# EspRelay.net
KiCad netlist of a schematic drawn in EAGLE
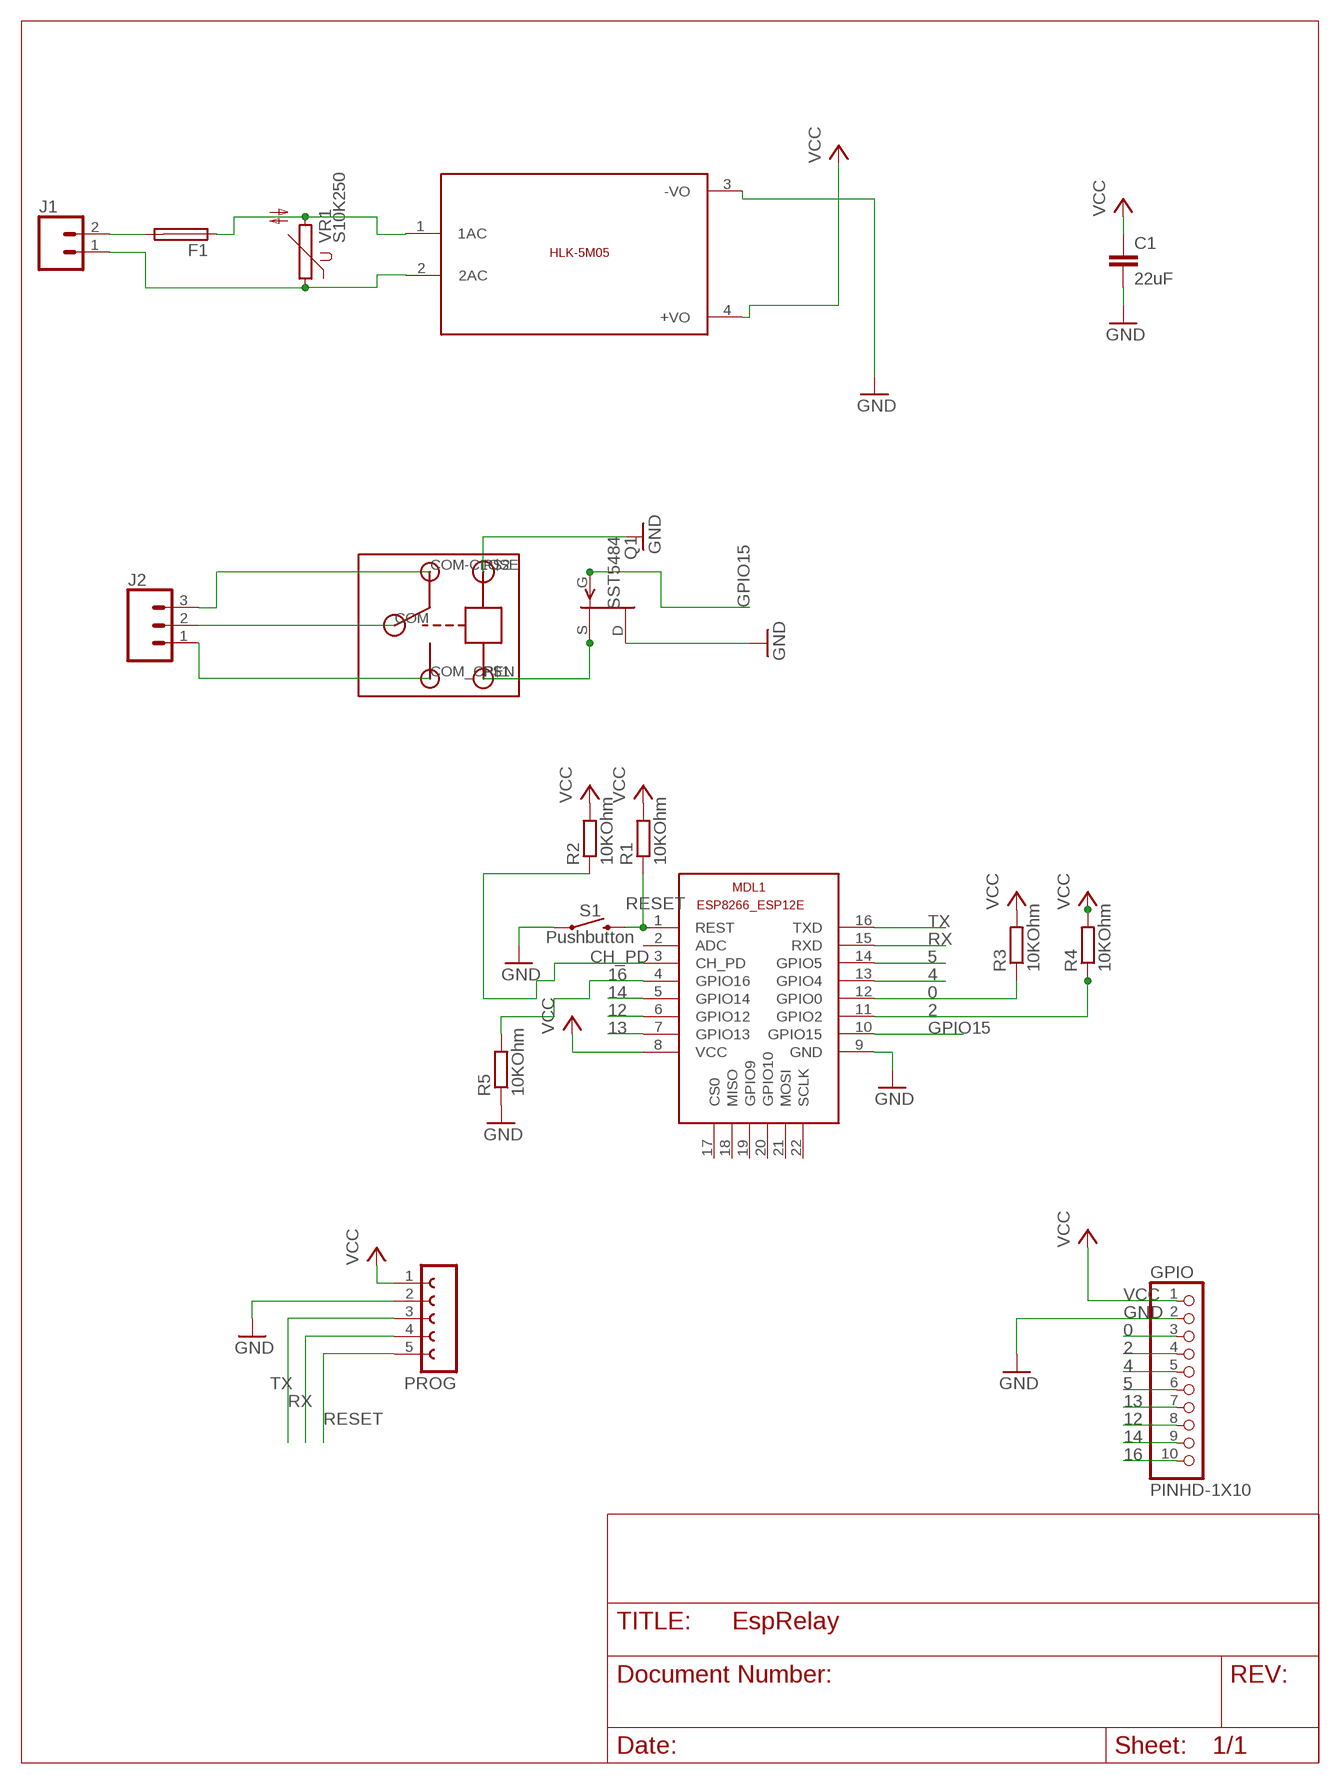
[diagram p0: schematic, sheet 1]

(export (version "E")
  (design (tool "Eeschema 10.0.6"))
  (components
    (comp (ref "C1")
      (value "22uF")
      (footprint "eagle-import:0402-CAP")
      (libsource (lib "eagle-import") (part "2.2UF-CERCAP-07888"))
    )
    (comp (ref "F1")
      (value "PICOFUSE")
      (footprint "eagle-import:PICOFUSE")
      (libsource (lib "eagle-import") (part "PICOFUSE"))
    )
    (comp (ref "GPIO")
      (value "PINHD-1X10")
      (footprint "eagle-import:1X10-BIG")
      (libsource (lib "eagle-import") (part "PINHD-1X10"))
    )
    (comp (ref "J1")
      (value "CONN_025MM")
      (footprint "eagle-import:SCREWTERMINAL-5MM-2")
      (libsource (lib "eagle-import") (part "CONN_025MM"))
    )
    (comp (ref "J2")
      (value "CONN_03-SCREW-5MM")
      (footprint "eagle-import:SCREWTERMINAL-5MM-3")
      (libsource (lib "eagle-import") (part "CONN_03-SCREW-5MM"))
    )
    (comp (ref "MDL1")
      (value "ESP8266-12EESP8266-ESP12E")
      (footprint "eagle-import:ESP8266-ESP12E")
      (libsource (lib "eagle-import") (part "ESP8266-12EESP8266-ESP12E"))
    )
    (comp (ref "PROG")
      (value "FE05-1")
      (footprint "eagle-import:FE05-1")
      (libsource (lib "eagle-import") (part "FE05-1"))
    )
    (comp (ref "Q1")
      (value "SST5484")
      (footprint "eagle-import:SOT23")
      (libsource (lib "eagle-import") (part "?548SST4"))
    )
    (comp (ref "R1")
      (value "10KOhm")
      (footprint "eagle-import:R0805")
      (libsource (lib "eagle-import") (part "R-EU_R0805"))
    )
    (comp (ref "R2")
      (value "10KOhm")
      (footprint "eagle-import:R0805")
      (libsource (lib "eagle-import") (part "R-EU_R0805"))
    )
    (comp (ref "R3")
      (value "10KOhm")
      (footprint "eagle-import:R0805")
      (libsource (lib "eagle-import") (part "R-EU_R0805"))
    )
    (comp (ref "R4")
      (value "10KOhm")
      (footprint "eagle-import:R0805")
      (libsource (lib "eagle-import") (part "R-EU_R0805"))
    )
    (comp (ref "R5")
      (value "10KOhm")
      (footprint "eagle-import:R0805")
      (libsource (lib "eagle-import") (part "R-EU_R0805"))
    )
    (comp (ref "S1")
      (value "Pushbutton")
      (footprint "eagle-import:TACTILE_SWITCH_SMD_6.0X3.5MM")
      (libsource (lib "eagle-import") (part "MOMENTARY-SWITCH-SPST-SMD-6.0X3.5MM"))
    )
    (comp (ref "U$1")
      (value "RELAY")
      (footprint "eagle-import:RELAY")
      (libsource (lib "eagle-import") (part "RELAY"))
    )
    (comp (ref "U$2")
      (value "5VDC/5W")
      (footprint "eagle-import:HLK-5M05")
      (libsource (lib "eagle-import") (part "HLK-5M05"))
    )
    (comp (ref "VR1")
      (value "S10K250")
      (footprint "eagle-import:S10K250")
      (libsource (lib "eagle-import") (part "S10K250"))
    )
  )
  (nets
    (net (code "1") (name "/0") (class "Default")
      (node (ref "GPIO") (pin "3") (pinfunction "3_3") (pintype "passive"))
      (node (ref "MDL1") (pin "12") (pinfunction "GPIO0_12") (pintype "bidirectional"))
      (node (ref "R3") (pin "1") (pinfunction "1_1") (pintype "passive"))
    )
    (net (code "2") (name "/2") (class "Default")
      (node (ref "GPIO") (pin "4") (pinfunction "4_4") (pintype "passive"))
      (node (ref "MDL1") (pin "11") (pinfunction "GPIO2_11") (pintype "bidirectional"))
      (node (ref "R4") (pin "1") (pinfunction "1_1") (pintype "passive"))
    )
    (net (code "3") (name "/4") (class "Default")
      (node (ref "GPIO") (pin "5") (pinfunction "5_5") (pintype "passive"))
      (node (ref "MDL1") (pin "13") (pinfunction "GPIO4_13") (pintype "bidirectional"))
    )
    (net (code "4") (name "/5") (class "Default")
      (node (ref "GPIO") (pin "6") (pinfunction "6_6") (pintype "passive"))
      (node (ref "MDL1") (pin "14") (pinfunction "GPIO5_14") (pintype "bidirectional"))
    )
    (net (code "5") (name "/12") (class "Default")
      (node (ref "GPIO") (pin "8") (pinfunction "8_8") (pintype "passive"))
      (node (ref "MDL1") (pin "6") (pinfunction "GPIO12_6") (pintype "bidirectional"))
    )
    (net (code "6") (name "/13") (class "Default")
      (node (ref "GPIO") (pin "7") (pinfunction "7_7") (pintype "passive"))
      (node (ref "MDL1") (pin "7") (pinfunction "GPIO13_7") (pintype "bidirectional"))
    )
    (net (code "7") (name "/14") (class "Default")
      (node (ref "GPIO") (pin "9") (pinfunction "9_9") (pintype "passive"))
      (node (ref "MDL1") (pin "5") (pinfunction "GPIO14_5") (pintype "bidirectional"))
    )
    (net (code "8") (name "/16") (class "Default")
      (node (ref "GPIO") (pin "10") (pinfunction "10_10") (pintype "passive"))
      (node (ref "MDL1") (pin "4") (pinfunction "GPIO16_4") (pintype "bidirectional"))
      (node (ref "R5") (pin "2") (pinfunction "2_2") (pintype "passive"))
    )
    (net (code "9") (name "/CH_PD") (class "Default")
      (node (ref "MDL1") (pin "3") (pinfunction "CH_PD_3") (pintype "bidirectional"))
      (node (ref "R2") (pin "1") (pinfunction "1_1") (pintype "passive"))
    )
    (net (code "10") (name "/GPIO15") (class "Default")
      (node (ref "MDL1") (pin "10") (pinfunction "GPIO15_10") (pintype "bidirectional"))
      (node (ref "Q1") (pin "3") (pinfunction "G_3") (pintype "passive"))
    )
    (net (code "11") (name "/RESET") (class "Default")
      (node (ref "MDL1") (pin "1") (pinfunction "REST_1") (pintype "bidirectional"))
      (node (ref "PROG") (pin "5") (pinfunction "5_5") (pintype "passive"))
      (node (ref "R1") (pin "1") (pinfunction "1_1") (pintype "passive"))
      (node (ref "S1") (pin "2") (pinfunction "2_2") (pintype "passive"))
    )
    (net (code "12") (name "/RX") (class "Default")
      (node (ref "MDL1") (pin "15") (pinfunction "RXD_15") (pintype "bidirectional"))
      (node (ref "PROG") (pin "4") (pinfunction "4_4") (pintype "passive"))
    )
    (net (code "13") (name "/TX") (class "Default")
      (node (ref "MDL1") (pin "16") (pinfunction "TXD_16") (pintype "bidirectional"))
      (node (ref "PROG") (pin "3") (pinfunction "3_3") (pintype "passive"))
    )
    (net (code "14") (name "GND") (class "Default")
      (node (ref "C1") (pin "2") (pinfunction "2_2") (pintype "passive"))
      (node (ref "GPIO") (pin "2") (pinfunction "2_2") (pintype "passive"))
      (node (ref "MDL1") (pin "9") (pinfunction "GND_9") (pintype "bidirectional"))
      (node (ref "PROG") (pin "2") (pinfunction "2_2") (pintype "passive"))
      (node (ref "Q1") (pin "1") (pinfunction "D_1") (pintype "passive"))
      (node (ref "R5") (pin "1") (pinfunction "1_1") (pintype "passive"))
      (node (ref "S1") (pin "1") (pinfunction "1_1") (pintype "passive"))
      (node (ref "U$1") (pin "P$2") (pinfunction "GND_P$2") (pintype "bidirectional"))
      (node (ref "U$2") (pin "3") (pinfunction "-VO_3") (pintype "bidirectional"))
    )
    (net (code "15") (name "Net-(F1-Pad2)") (class "Default")
      (node (ref "F1") (pin "2") (pinfunction "2_2") (pintype "passive"))
      (node (ref "J1") (pin "2") (pinfunction "2_2") (pintype "passive"))
    )
    (net (code "16") (name "Net-(J2-Pad2)") (class "Default")
      (node (ref "J2") (pin "2") (pinfunction "2_2") (pintype "passive"))
      (node (ref "U$1") (pin "COM") (pinfunction "COM_COM") (pintype "bidirectional"))
    )
    (net (code "17") (name "Net-(J2-Pad3)") (class "Default")
      (node (ref "J2") (pin "3") (pinfunction "3_3") (pintype "passive"))
      (node (ref "U$1") (pin "COM-CLOSE") (pinfunction "COM-CLOSE_COM-CLOSE") (pintype "bidirectional"))
    )
    (net (code "18") (name "Net-(Q1-S)") (class "Default")
      (node (ref "Q1") (pin "2") (pinfunction "S_2") (pintype "passive"))
      (node (ref "U$1") (pin "P$1") (pinfunction "IN_P$1") (pintype "bidirectional"))
    )
    (net (code "19") (name "Net-(U$1-COM-OPEN)") (class "Default")
      (node (ref "J2") (pin "1") (pinfunction "1_1") (pintype "passive"))
      (node (ref "U$1") (pin "COM_CPEN") (pinfunction "COM-OPEN_COM_CPEN") (pintype "bidirectional"))
    )
    (net (code "20") (name "Net-(U$2-1AC)") (class "Default")
      (node (ref "F1") (pin "1") (pinfunction "1_1") (pintype "passive"))
      (node (ref "U$2") (pin "1") (pinfunction "1AC_1") (pintype "bidirectional"))
      (node (ref "VR1") (pin "2") (pinfunction "2_2") (pintype "passive"))
    )
    (net (code "21") (name "Net-(U$2-2AC)") (class "Default")
      (node (ref "J1") (pin "1") (pinfunction "1_1") (pintype "passive"))
      (node (ref "U$2") (pin "2") (pinfunction "2AC_2") (pintype "bidirectional"))
      (node (ref "VR1") (pin "1") (pinfunction "1_1") (pintype "passive"))
    )
    (net (code "22") (name "VCC") (class "Default")
      (node (ref "C1") (pin "1") (pinfunction "1_1") (pintype "passive"))
      (node (ref "GPIO") (pin "1") (pinfunction "1_1") (pintype "passive"))
      (node (ref "MDL1") (pin "8") (pinfunction "VCC_8") (pintype "bidirectional"))
      (node (ref "PROG") (pin "1") (pinfunction "1_1") (pintype "passive"))
      (node (ref "R1") (pin "2") (pinfunction "2_2") (pintype "passive"))
      (node (ref "R2") (pin "2") (pinfunction "2_2") (pintype "passive"))
      (node (ref "R3") (pin "2") (pinfunction "2_2") (pintype "passive"))
      (node (ref "R4") (pin "2") (pinfunction "2_2") (pintype "passive"))
      (node (ref "U$2") (pin "4") (pinfunction "+VO_4") (pintype "bidirectional"))
    )
    (net (code "23") (name "unconnected-(MDL1-ADC-Pad2)") (class "Default")
      (node (ref "MDL1") (pin "2") (pinfunction "ADC_2") (pintype "bidirectional"))
    )
    (net (code "24") (name "unconnected-(MDL1-CS0-Pad17)") (class "Default")
      (node (ref "MDL1") (pin "17") (pinfunction "CS0_17") (pintype "bidirectional"))
    )
    (net (code "25") (name "unconnected-(MDL1-GPIO9-Pad19)") (class "Default")
      (node (ref "MDL1") (pin "19") (pinfunction "GPIO9_19") (pintype "bidirectional"))
    )
    (net (code "26") (name "unconnected-(MDL1-GPIO10-Pad20)") (class "Default")
      (node (ref "MDL1") (pin "20") (pinfunction "GPIO10_20") (pintype "bidirectional"))
    )
    (net (code "27") (name "unconnected-(MDL1-MISO-Pad18)") (class "Default")
      (node (ref "MDL1") (pin "18") (pinfunction "MISO_18") (pintype "bidirectional"))
    )
    (net (code "28") (name "unconnected-(MDL1-MOSI-Pad21)") (class "Default")
      (node (ref "MDL1") (pin "21") (pinfunction "MOSI_21") (pintype "bidirectional"))
    )
    (net (code "29") (name "unconnected-(MDL1-SCLK-Pad22)") (class "Default")
      (node (ref "MDL1") (pin "22") (pinfunction "SCLK_22") (pintype "bidirectional"))
    )
  )
)
